# TLV493D-Board_RevB.net
KiCad netlist of a schematic drawn in EAGLE
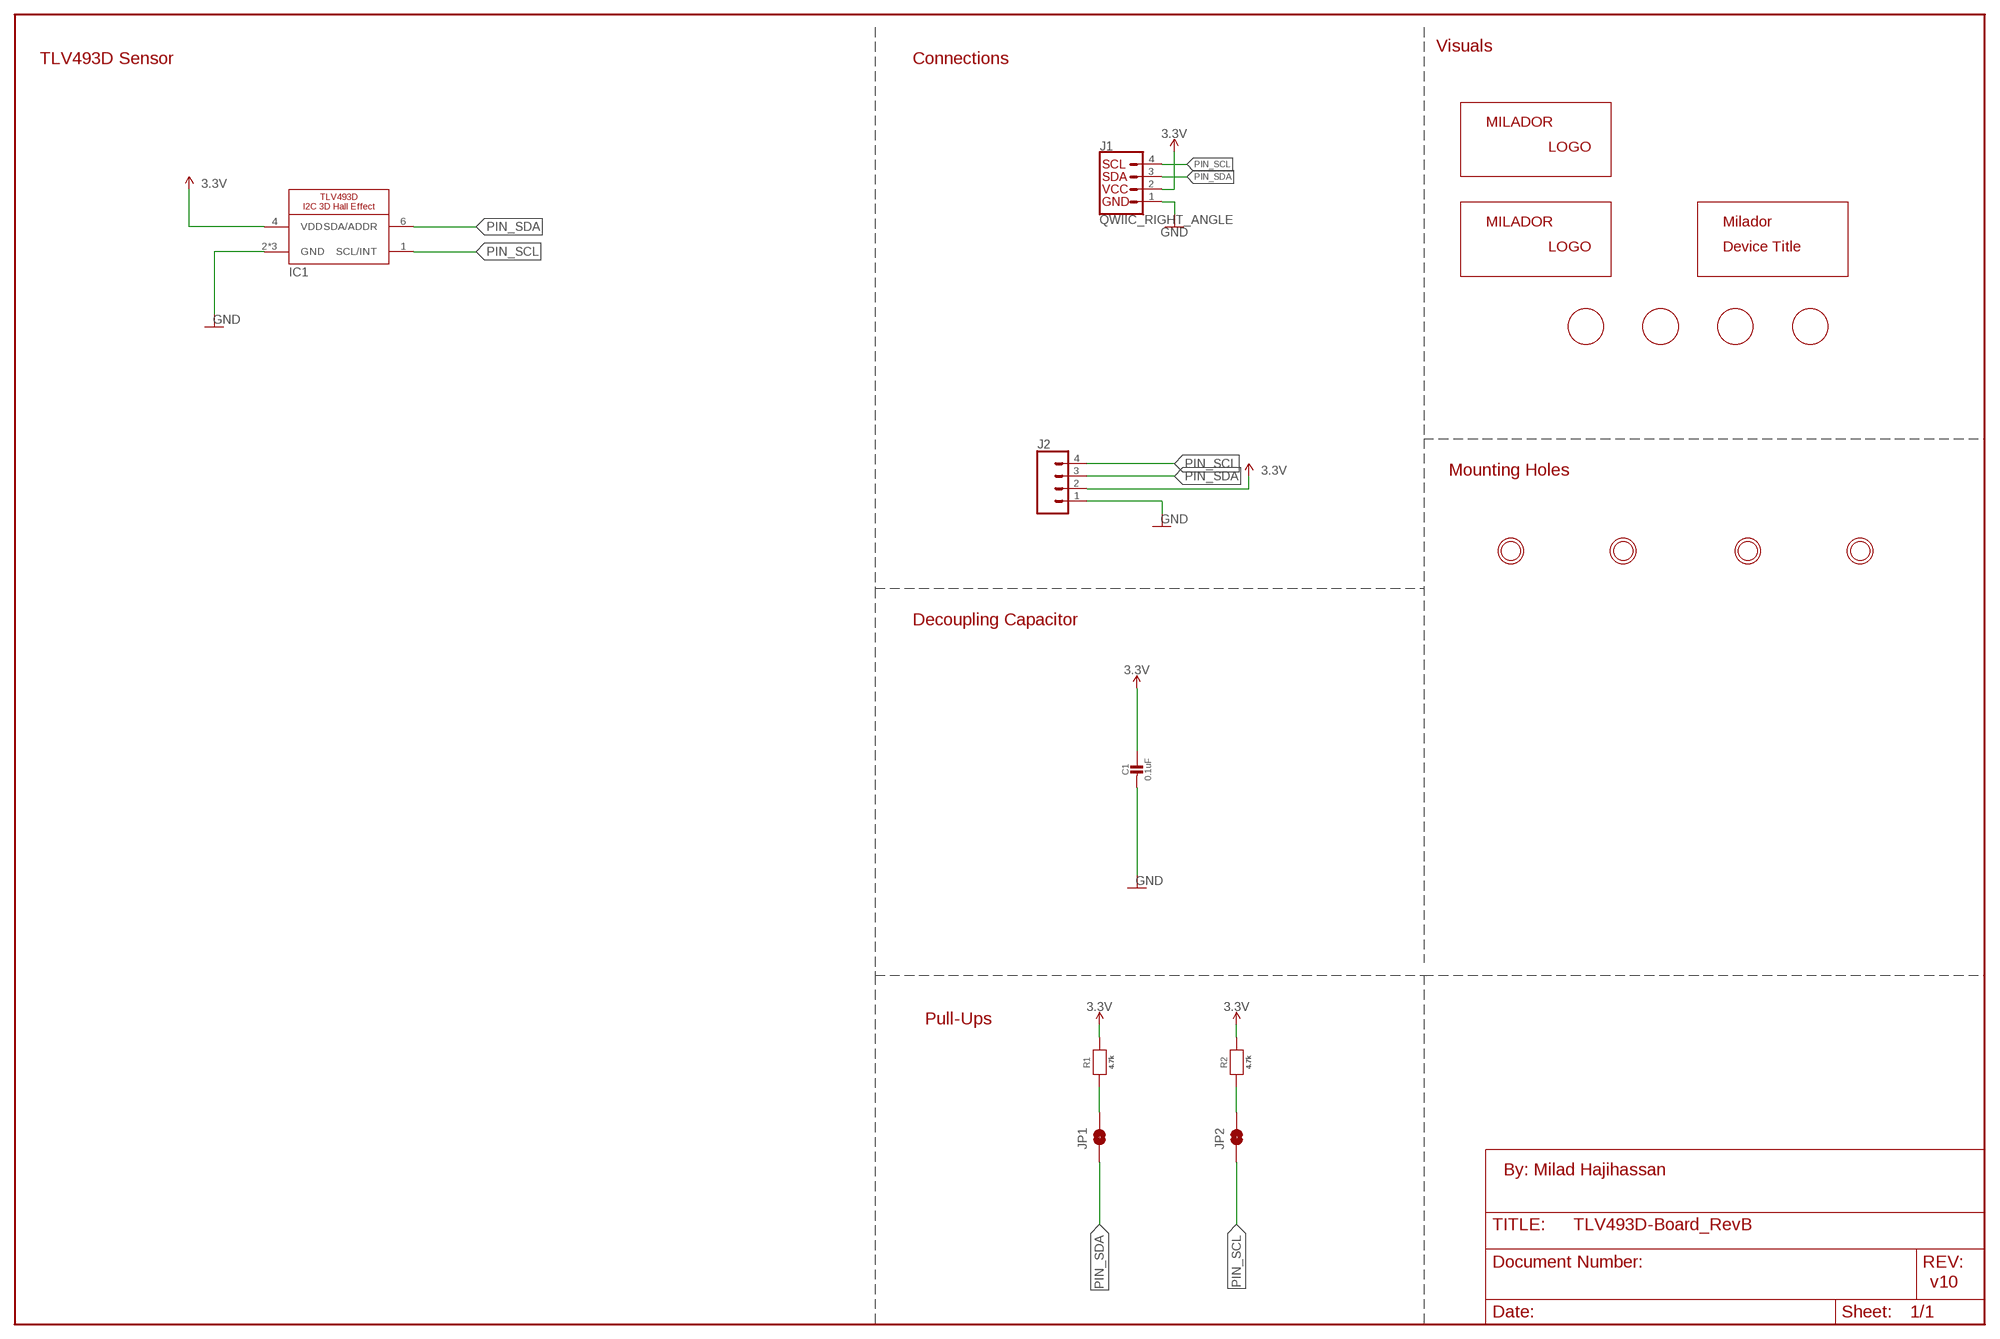
[diagram p0: schematic, sheet 1]

(export (version "E")
  (design (tool "Eeschema 10.0.6"))
  (components
    (comp (ref "C1")
      (value "0.1uF")
      (footprint "eagle-import:0805")
      (libsource (lib "eagle-import") (part "CAP_CERAMIC-0805"))
    )
    (comp (ref "IC1")
      (value "TLV493D")
      (footprint "eagle-import:SOT23-6")
      (libsource (lib "eagle-import") (part "TLV493D"))
    )
    (comp (ref "J1")
      (value "QWIIC_RIGHT_ANGLE")
      (footprint "eagle-import:CONNECTORS_JST04_1MM_RA")
      (fields (field (name "PROD_ID") "CONN-13694"))
      (libsource (lib "eagle-import") (part "QWIIC_CONNECTORSJS-1MM"))
    )
    (comp (ref "J2")
      (value "CONNECTORS_CONN_041X04_NO_SILK")
      (footprint "eagle-import:CONNECTORS_1X04_NO_SILK")
      (libsource (lib "eagle-import") (part "CONNECTORS_CONN_041X04_NO_SILK"))
    )
    (comp (ref "JP1")
      (value "JUMPERS-SMT_2_NC_TRACE_SILK")
      (footprint "eagle-import:JUMPERS_SMT-JUMPER_2_NC_TRACE_SILK")
      (libsource (lib "eagle-import") (part "JUMPERS-SMT_2_NC_TRACE_SILK"))
    )
    (comp (ref "JP2")
      (value "JUMPERS-SMT_2_NC_TRACE_SILK")
      (footprint "eagle-import:JUMPERS_SMT-JUMPER_2_NC_TRACE_SILK")
      (libsource (lib "eagle-import") (part "JUMPERS-SMT_2_NC_TRACE_SILK"))
    )
    (comp (ref "LABEL_3V_BOTTOM")
      (value "MILADOR-LABEL-3V")
      (footprint "eagle-import:LABEL-3V")
      (libsource (lib "eagle-import") (part "MILADOR-LABEL-3V"))
    )
    (comp (ref "LABEL_GND_BOTTOM")
      (value "MILADOR-LABEL-GND")
      (footprint "eagle-import:LABEL-GND")
      (libsource (lib "eagle-import") (part "MILADOR-LABEL-GND"))
    )
    (comp (ref "LABEL_MILADOR_BOTTOM")
      (value "MILADOR-LOGO-")
      (footprint "eagle-import:MILADOR_LOGO1")
      (libsource (lib "eagle-import") (part "MILADOR-LOGO-"))
    )
    (comp (ref "LABEL_MILADOR_TLV493D_BOTTOM")
      (value "MILADOR-DEVICE-TLV493D_BOARD")
      (footprint "eagle-import:MILADOR_TLV493D_BOARD")
      (libsource (lib "eagle-import") (part "MILADOR-DEVICE-TLV493D_BOARD"))
    )
    (comp (ref "LABEL_MILADOR_TOP")
      (value "MILADOR-LOGO-")
      (footprint "eagle-import:MILADOR_LOGO1")
      (libsource (lib "eagle-import") (part "MILADOR-LOGO-"))
    )
    (comp (ref "LABE_SCL_BOTTOM")
      (value "MILADOR-LABEL-SCL")
      (footprint "eagle-import:LABEL-SCL")
      (libsource (lib "eagle-import") (part "MILADOR-LABEL-SCL"))
    )
    (comp (ref "LABE_SDA_BOTTOM")
      (value "MILADOR-LABEL-SDA")
      (footprint "eagle-import:LABEL-SDA")
      (libsource (lib "eagle-import") (part "MILADOR-LABEL-SDA"))
    )
    (comp (ref "M1")
      (value "MOUNTINGHOLE2.5")
      (footprint "eagle-import:MOUNTINGHOLE_2.5_PLATED")
      (libsource (lib "eagle-import") (part "MOUNTINGHOLE2.5"))
    )
    (comp (ref "M2")
      (value "MOUNTINGHOLE2.5")
      (footprint "eagle-import:MOUNTINGHOLE_2.5_PLATED")
      (libsource (lib "eagle-import") (part "MOUNTINGHOLE2.5"))
    )
    (comp (ref "M3")
      (value "MOUNTINGHOLE2.5")
      (footprint "eagle-import:MOUNTINGHOLE_2.5_PLATED")
      (libsource (lib "eagle-import") (part "MOUNTINGHOLE2.5"))
    )
    (comp (ref "M4")
      (value "MOUNTINGHOLE2.5")
      (footprint "eagle-import:MOUNTINGHOLE_2.5_PLATED")
      (libsource (lib "eagle-import") (part "MOUNTINGHOLE2.5"))
    )
    (comp (ref "R1")
      (value "4.7k")
      (footprint "eagle-import:0603-NO")
      (libsource (lib "eagle-import") (part "RESISTOR-0603-NOOUT"))
    )
    (comp (ref "R2")
      (value "4.7k")
      (footprint "eagle-import:0603-NO")
      (libsource (lib "eagle-import") (part "RESISTOR-0603-NOOUT"))
    )
  )
  (nets
    (net (code "1") (name "3.3V") (class "Default")
      (node (ref "C1") (pin "1") (pinfunction "1_1") (pintype "passive"))
      (node (ref "IC1") (pin "4") (pinfunction "VDD_4") (pintype "power_in"))
      (node (ref "J1") (pin "2") (pinfunction "2_2") (pintype "power_in"))
      (node (ref "J2") (pin "2") (pinfunction "2_2") (pintype "passive"))
      (node (ref "R1") (pin "2") (pinfunction "2_2") (pintype "passive"))
      (node (ref "R2") (pin "2") (pinfunction "2_2") (pintype "passive"))
    )
    (net (code "2") (name "GND") (class "Default")
      (node (ref "C1") (pin "2") (pinfunction "2_2") (pintype "passive"))
      (node (ref "IC1") (pin "2") (pinfunction "GND_2") (pintype "power_in"))
      (node (ref "IC1") (pin "3") (pinfunction "GND_3") (pintype "power_in"))
      (node (ref "IC1") (pin "5") (pinfunction "GND_5") (pintype "power_in"))
      (node (ref "J1") (pin "1") (pinfunction "1_1") (pintype "power_in"))
      (node (ref "J2") (pin "1") (pinfunction "1_1") (pintype "passive"))
    )
    (net (code "3") (name "Net-(JP1-Pad2)") (class "Default")
      (node (ref "JP1") (pin "2") (pinfunction "2_2") (pintype "passive"))
      (node (ref "R1") (pin "1") (pinfunction "1_1") (pintype "passive"))
    )
    (net (code "4") (name "Net-(JP2-Pad2)") (class "Default")
      (node (ref "JP2") (pin "2") (pinfunction "2_2") (pintype "passive"))
      (node (ref "R2") (pin "1") (pinfunction "1_1") (pintype "passive"))
    )
    (net (code "5") (name "PIN_SCL") (class "Default")
      (node (ref "IC1") (pin "1") (pinfunction "SCL/INT_1") (pintype "bidirectional"))
      (node (ref "J1") (pin "4") (pinfunction "4_4") (pintype "passive"))
      (node (ref "J2") (pin "4") (pinfunction "4_4") (pintype "passive"))
      (node (ref "JP2") (pin "1") (pinfunction "1_1") (pintype "passive"))
    )
    (net (code "6") (name "PIN_SDA") (class "Default")
      (node (ref "IC1") (pin "6") (pinfunction "SDA/ADDR_6") (pintype "bidirectional"))
      (node (ref "J1") (pin "3") (pinfunction "3_3") (pintype "passive"))
      (node (ref "J2") (pin "3") (pinfunction "3_3") (pintype "passive"))
      (node (ref "JP1") (pin "1") (pinfunction "1_1") (pintype "passive"))
    )
  )
)
